# Nokia1600.net
KiCad netlist of a schematic drawn in EAGLE
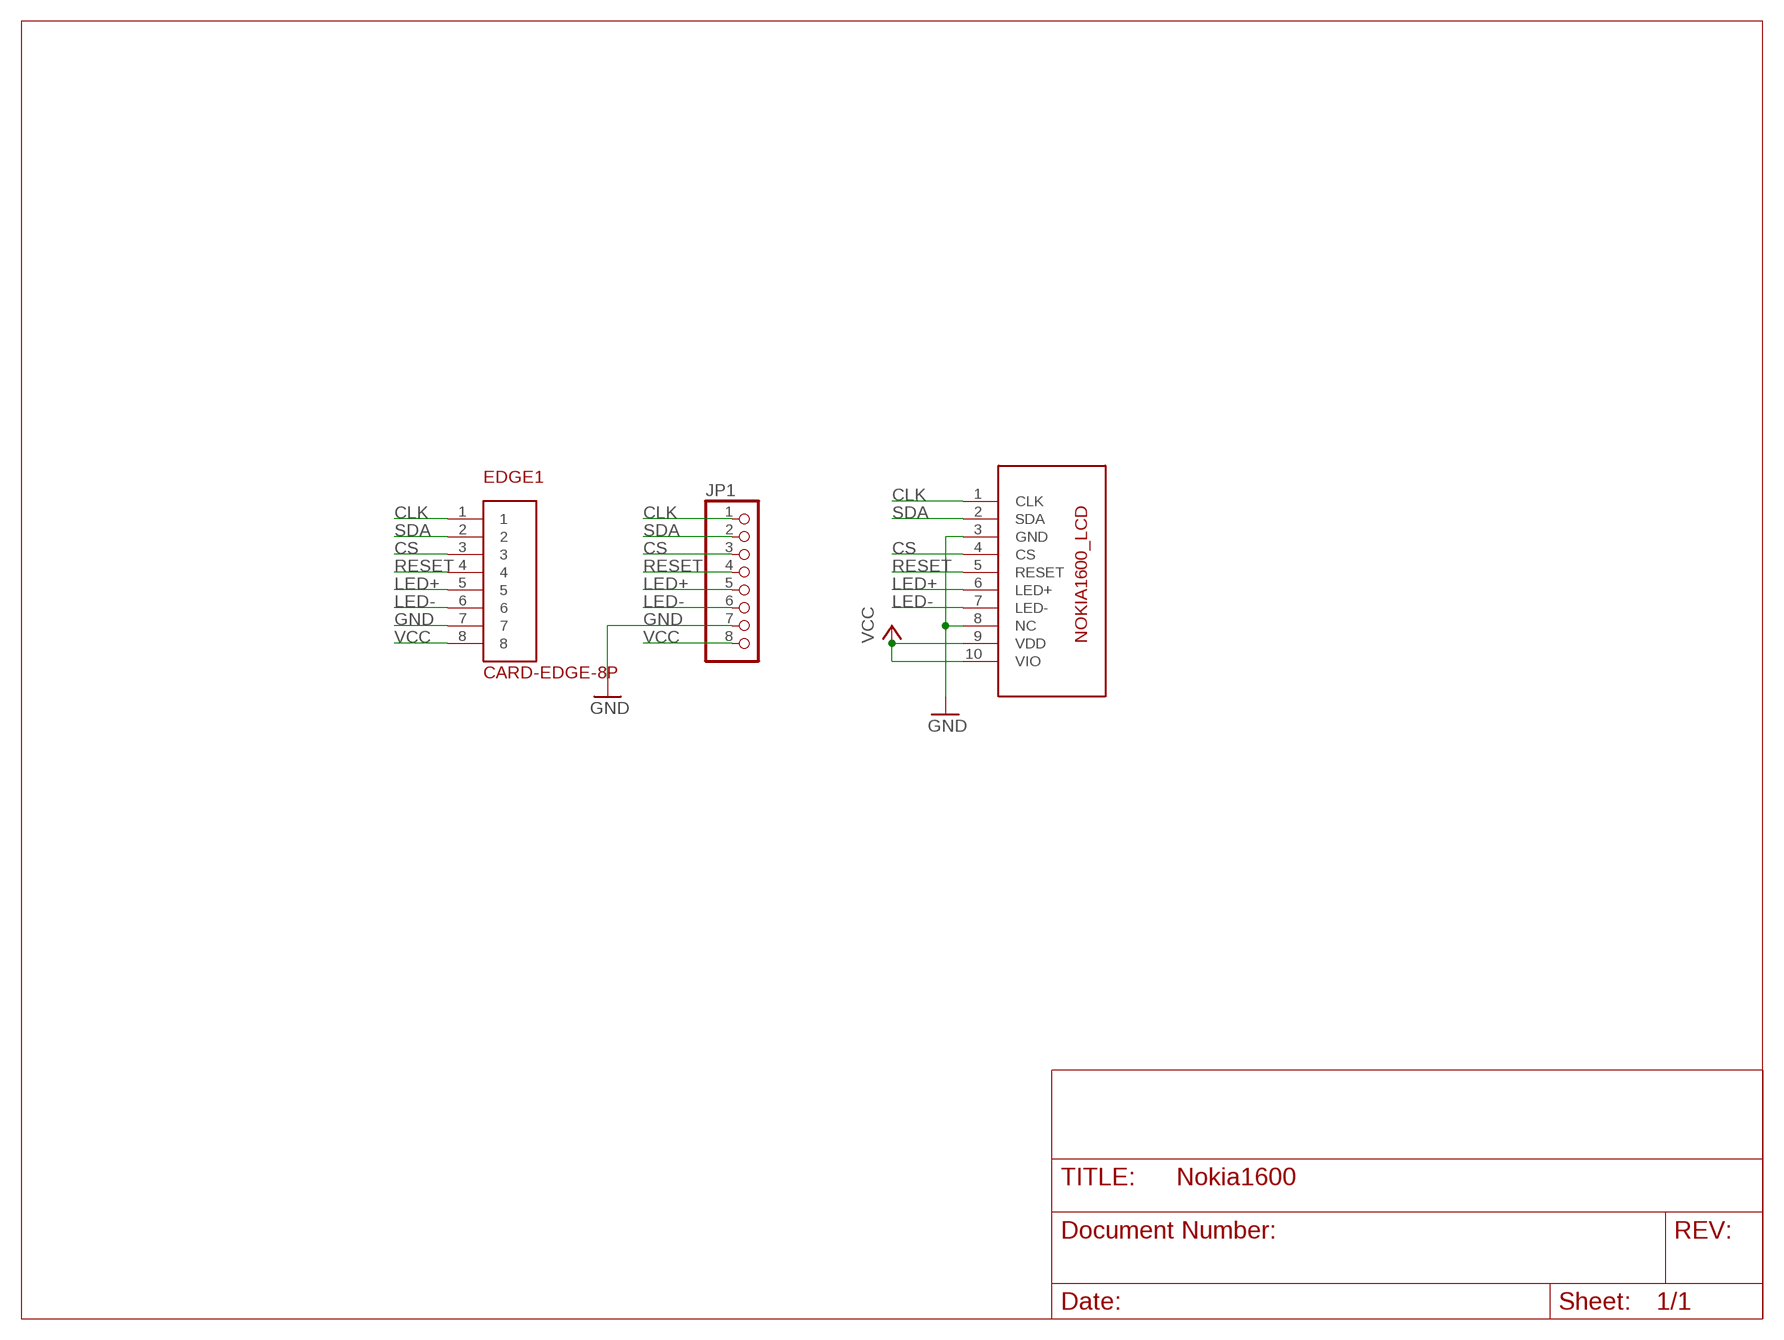
[diagram p0: schematic, sheet 1]

(export (version "E")
  (design (tool "Eeschema 10.0.6"))
  (components
    (comp (ref "EDGE1")
      (value "CARD-EDGE-8P")
      (footprint "eagle-import:DUOPLUG-8P-KEYED")
      (libsource (lib "eagle-import") (part "DUOPLUG-8P-KEYEDCARD-EDGE-8P"))
    )
    (comp (ref "JP1")
      (value "HEADER-1X8ROUND")
      (footprint "eagle-import:1X08_ROUND")
      (libsource (lib "eagle-import") (part "HEADER-1X8ROUND"))
    )
    (comp (ref "U$1")
      (value "NOKIA1600_LCD")
      (footprint "eagle-import:NOKIA1600_LCD")
      (libsource (lib "eagle-import") (part "NOKIA1600_LCD"))
    )
  )
  (nets
    (net (code "1") (name "/CLK") (class "Default")
      (node (ref "EDGE1") (pin "1") (pinfunction "1_1") (pintype "bidirectional"))
      (node (ref "JP1") (pin "1") (pinfunction "1_1") (pintype "passive"))
      (node (ref "U$1") (pin "1") (pinfunction "CLK_1") (pintype "bidirectional"))
    )
    (net (code "2") (name "/CS") (class "Default")
      (node (ref "EDGE1") (pin "3") (pinfunction "3_3") (pintype "bidirectional"))
      (node (ref "JP1") (pin "3") (pinfunction "3_3") (pintype "passive"))
      (node (ref "U$1") (pin "4") (pinfunction "CS_4") (pintype "bidirectional"))
    )
    (net (code "3") (name "/LED+") (class "Default")
      (node (ref "EDGE1") (pin "5") (pinfunction "5_5") (pintype "bidirectional"))
      (node (ref "JP1") (pin "5") (pinfunction "5_5") (pintype "passive"))
      (node (ref "U$1") (pin "6") (pinfunction "LED+_6") (pintype "bidirectional"))
    )
    (net (code "4") (name "/LED-") (class "Default")
      (node (ref "EDGE1") (pin "6") (pinfunction "6_6") (pintype "bidirectional"))
      (node (ref "JP1") (pin "6") (pinfunction "6_6") (pintype "passive"))
      (node (ref "U$1") (pin "7") (pinfunction "LED-_7") (pintype "bidirectional"))
    )
    (net (code "5") (name "/RESET") (class "Default")
      (node (ref "EDGE1") (pin "4") (pinfunction "4_4") (pintype "bidirectional"))
      (node (ref "JP1") (pin "4") (pinfunction "4_4") (pintype "passive"))
      (node (ref "U$1") (pin "5") (pinfunction "RESET_5") (pintype "bidirectional"))
    )
    (net (code "6") (name "/SDA") (class "Default")
      (node (ref "EDGE1") (pin "2") (pinfunction "2_2") (pintype "bidirectional"))
      (node (ref "JP1") (pin "2") (pinfunction "2_2") (pintype "passive"))
      (node (ref "U$1") (pin "2") (pinfunction "SDA_2") (pintype "bidirectional"))
    )
    (net (code "7") (name "GND") (class "Default")
      (node (ref "EDGE1") (pin "7") (pinfunction "7_7") (pintype "bidirectional"))
      (node (ref "JP1") (pin "7") (pinfunction "7_7") (pintype "passive"))
      (node (ref "U$1") (pin "3") (pinfunction "GND_3") (pintype "bidirectional"))
      (node (ref "U$1") (pin "8") (pinfunction "NC_8") (pintype "bidirectional"))
    )
    (net (code "8") (name "VCC") (class "Default")
      (node (ref "EDGE1") (pin "8") (pinfunction "8_8") (pintype "bidirectional"))
      (node (ref "JP1") (pin "8") (pinfunction "8_8") (pintype "passive"))
      (node (ref "U$1") (pin "10") (pinfunction "VIO_10") (pintype "bidirectional"))
      (node (ref "U$1") (pin "9") (pinfunction "VDD_9") (pintype "bidirectional"))
    )
  )
)
